# CoinControllerV1.net
KiCad netlist of a schematic drawn in EAGLE
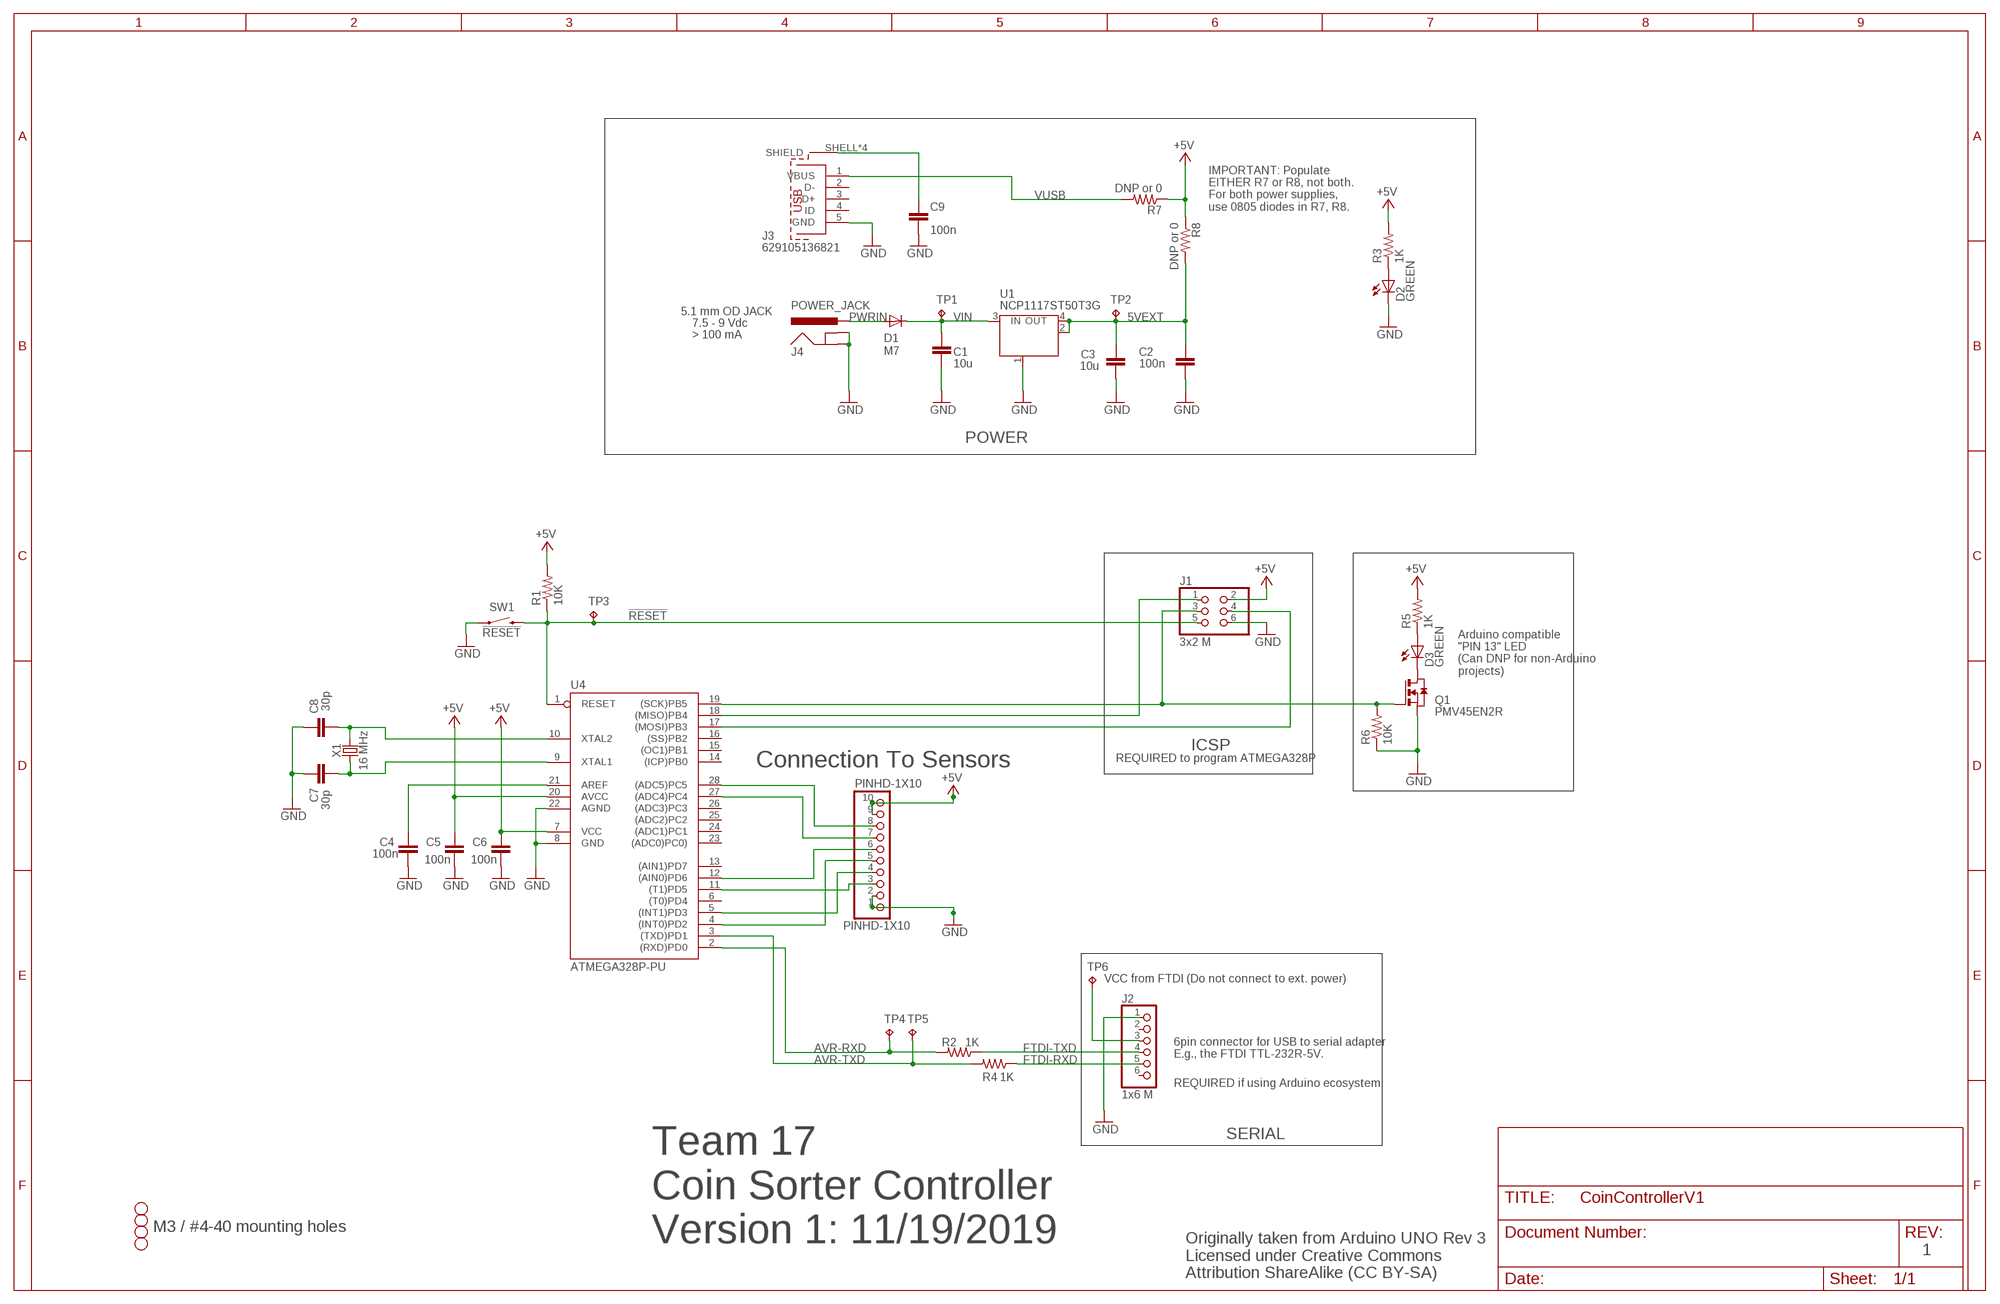
[diagram p0: schematic, sheet 1]

(export (version "E")
  (design (tool "Eeschema 10.0.6"))
  (components
    (comp (ref "C1")
      (value "10u")
      (footprint "eagle-import:C0805K")
      (fields (field (name "MFR") "Samsung") (field (name "MPN") "CL21A106KOQNNNG"))
      (libsource (lib "eagle-import") (part "C-EUC0805K"))
    )
    (comp (ref "C2")
      (value "100n")
      (footprint "eagle-import:C0805K")
      (fields (field (name "MFR") "Samsung") (field (name "MPN") "CL21B104KBCNNNC"))
      (libsource (lib "eagle-import") (part "C-EUC0805K"))
    )
    (comp (ref "C3")
      (value "10u")
      (footprint "eagle-import:C0805K")
      (fields (field (name "MFR") "Samsung") (field (name "MPN") "CL21A106KOQNNNG"))
      (libsource (lib "eagle-import") (part "C-EUC0805K"))
    )
    (comp (ref "C4")
      (value "100n")
      (footprint "eagle-import:C0805K")
      (fields (field (name "MFR") "Samsung") (field (name "MPN") "CL21B104KBCNNNC"))
      (libsource (lib "eagle-import") (part "C-EUC0805K"))
    )
    (comp (ref "C5")
      (value "100n")
      (footprint "eagle-import:C0805K")
      (fields (field (name "MFR") "Samsung") (field (name "MPN") "CL21B104KBCNNNC"))
      (libsource (lib "eagle-import") (part "C-EUC0805K"))
    )
    (comp (ref "C6")
      (value "100n")
      (footprint "eagle-import:C0805K")
      (fields (field (name "MFR") "Samsung") (field (name "MPN") "CL21B104KBCNNNC"))
      (libsource (lib "eagle-import") (part "C-EUC0805K"))
    )
    (comp (ref "C7")
      (value "30p")
      (footprint "eagle-import:C0805K")
      (fields (field (name "MFR") "Samsung") (field (name "MPN") "CL21C180JBANNNC"))
      (libsource (lib "eagle-import") (part "C-EUC0805K"))
    )
    (comp (ref "C8")
      (value "30p")
      (footprint "eagle-import:C0805K")
      (fields (field (name "MFR") "Samsung") (field (name "MPN") "CL21C300JBANNNC"))
      (libsource (lib "eagle-import") (part "C-EUC0805K"))
    )
    (comp (ref "C9")
      (value "100n")
      (footprint "eagle-import:C0805K")
      (fields (field (name "MFR") "Samsung") (field (name "MPN") "CL21B104KBCNNNC"))
      (libsource (lib "eagle-import") (part "C-EUC0805K"))
    )
    (comp (ref "D1")
      (value "M7")
      (footprint "eagle-import:SMB")
      (fields (field (name "MFR") "SMC Diode") (field (name "MPN") "10BQ030TR"))
      (libsource (lib "eagle-import") (part "DIODE-SMB"))
    )
    (comp (ref "D2")
      (value "GREEN")
      (footprint "eagle-import:CHIP-LED0805")
      (fields (field (name "MFR") "Würth Elektronik") (field (name "MPN") "150080GS75000"))
      (libsource (lib "eagle-import") (part "LEDCHIP-LED0805"))
    )
    (comp (ref "D3")
      (value "GREEN")
      (footprint "eagle-import:CHIP-LED0805")
      (fields (field (name "MFR") "Würth Elektronik") (field (name "MPN") "150080GS75000"))
      (libsource (lib "eagle-import") (part "LEDCHIP-LED0805"))
    )
    (comp (ref "H1")
      (value "STAND-OFF")
      (footprint "eagle-import:STAND-OFF")
      (libsource (lib "eagle-import") (part "STAND-OFF"))
    )
    (comp (ref "H2")
      (value "STAND-OFF")
      (footprint "eagle-import:STAND-OFF")
      (libsource (lib "eagle-import") (part "STAND-OFF"))
    )
    (comp (ref "H3")
      (value "STAND-OFF")
      (footprint "eagle-import:STAND-OFF")
      (libsource (lib "eagle-import") (part "STAND-OFF"))
    )
    (comp (ref "H4")
      (value "STAND-OFF")
      (footprint "eagle-import:STAND-OFF")
      (libsource (lib "eagle-import") (part "STAND-OFF"))
    )
    (comp (ref "J1")
      (value "3x2 M")
      (footprint "eagle-import:2X03")
      (fields (field (name "MFR") "Harwin") (field (name "MPN") "M20-9980345"))
      (libsource (lib "eagle-import") (part "PINHD-2X3"))
    )
    (comp (ref "J2")
      (value "1x6 M")
      (footprint "eagle-import:1X06")
      (fields (field (name "MFR") "Sullins") (field (name "MPN") "PRPC006SAAN-RC"))
      (libsource (lib "eagle-import") (part "PINHD-1X6"))
    )
    (comp (ref "J3")
      (value "629105136821")
      (footprint "eagle-import:629105136821")
      (fields (field (name "MFR") "Wurth"))
      (libsource (lib "eagle-import") (part "629105136821"))
    )
    (comp (ref "J4")
      (value "POWER_JACK")
      (footprint "eagle-import:POWER_JACK_PTH")
      (fields (field (name "MFR") "CUI") (field (name "MPN") "PJ-202A"))
      (libsource (lib "eagle-import") (part "POWER_JACK"))
    )
    (comp (ref "PINHD-1X10")
      (value "PINHD-1X10")
      (footprint "eagle-import:1X10-BIG")
      (libsource (lib "eagle-import") (part "PINHD-1X10"))
    )
    (comp (ref "Q1")
      (value "PMV45EN2R")
      (footprint "eagle-import:SOT-23")
      (fields (field (name "MFR") "Nexperia") (field (name "MPN") "PMV45EN2R"))
      (libsource (lib "eagle-import") (part "NMOSSOT23"))
    )
    (comp (ref "R1")
      (value "10K")
      (footprint "eagle-import:R0805")
      (fields (field (name "MFR") "Yageo") (field (name "MPN") "RC0805FR-0710KL"))
      (libsource (lib "eagle-import") (part "R-US_R0805"))
    )
    (comp (ref "R2")
      (value "1K")
      (footprint "eagle-import:R0805")
      (fields (field (name "MFR") "Yageo") (field (name "MPN") "RC0805FR-071KL"))
      (libsource (lib "eagle-import") (part "R-US_R0805"))
    )
    (comp (ref "R3")
      (value "1K")
      (footprint "eagle-import:R0805")
      (fields (field (name "MFR") "Yageo") (field (name "MPN") "RC0805FR-071KL"))
      (libsource (lib "eagle-import") (part "R-US_R0805"))
    )
    (comp (ref "R4")
      (value "1K")
      (footprint "eagle-import:R0805")
      (fields (field (name "MFR") "Yageo") (field (name "MPN") "RC0805FR-071KL"))
      (libsource (lib "eagle-import") (part "R-US_R0805"))
    )
    (comp (ref "R5")
      (value "1K")
      (footprint "eagle-import:R0805")
      (fields (field (name "MFR") "Yageo") (field (name "MPN") "RC0805FR-071KL"))
      (libsource (lib "eagle-import") (part "R-US_R0805"))
    )
    (comp (ref "R6")
      (value "10K")
      (footprint "eagle-import:R0805")
      (fields (field (name "MFR") "Yageo") (field (name "MPN") "RC0805FR-0710KL"))
      (libsource (lib "eagle-import") (part "R-US_R0805"))
    )
    (comp (ref "R7")
      (value "DNP or 0")
      (footprint "eagle-import:R0805")
      (fields (field (name "MFR") "Yageo") (field (name "MPN") "RC0805JR-070RL"))
      (libsource (lib "eagle-import") (part "R-US_R0805"))
    )
    (comp (ref "R8")
      (value "DNP or 0")
      (footprint "eagle-import:R0805")
      (fields (field (name "MFR") "Yageo") (field (name "MPN") "RC0805JR-070RL"))
      (libsource (lib "eagle-import") (part "R-US_R0805"))
    )
    (comp (ref "SW1")
      (value "!RESET")
      (footprint "eagle-import:TACTILE_SWITCH_SMD")
      (fields (field (name "MFR") "C&K") (field (name "MPN") "RS-187R05A2-DS MT RT"))
      (libsource (lib "eagle-import") (part "SWITCH-MOMENTARY-2SMD"))
    )
    (comp (ref "TP1")
      (value "TPPAD1-13")
      (footprint "eagle-import:P1-13")
      (libsource (lib "eagle-import") (part "TPPAD1-13"))
    )
    (comp (ref "TP2")
      (value "TPPAD1-13")
      (footprint "eagle-import:P1-13")
      (libsource (lib "eagle-import") (part "TPPAD1-13"))
    )
    (comp (ref "TP3")
      (value "TPPAD1-13")
      (footprint "eagle-import:P1-13")
      (libsource (lib "eagle-import") (part "TPPAD1-13"))
    )
    (comp (ref "TP4")
      (value "TPPAD1-13")
      (footprint "eagle-import:P1-13")
      (libsource (lib "eagle-import") (part "TPPAD1-13"))
    )
    (comp (ref "TP5")
      (value "TPPAD1-13")
      (footprint "eagle-import:P1-13")
      (libsource (lib "eagle-import") (part "TPPAD1-13"))
    )
    (comp (ref "TP6")
      (value "TPPAD1-13")
      (footprint "eagle-import:P1-13")
      (libsource (lib "eagle-import") (part "TPPAD1-13"))
    )
    (comp (ref "U1")
      (value "NCP1117ST50T3G")
      (footprint "eagle-import:SOT223")
      (fields (field (name "MFR") "ON Semiconductor"))
      (libsource (lib "eagle-import") (part "MC33269ST-3.3T3"))
    )
    (comp (ref "U4")
      (value "ATMEGA328P-PU")
      (footprint "eagle-import:DIL28-3")
      (fields (field (name "MFR") "Microchip"))
      (libsource (lib "eagle-import") (part "ATMEGA328P-PU"))
    )
    (comp (ref "X1")
      (value "16 MHz")
      (footprint "eagle-import:HC49UP")
      (fields (field (name "MFR") "ECS") (field (name "MPN") "ECS-160-18-5PX-TR"))
      (libsource (lib "eagle-import") (part "CRYSTALSMD-HC49UP"))
    )
  )
  (nets
    (net (code "1") (name "+5V") (class "Default")
      (node (ref "C5") (pin "2") (pinfunction "2_2") (pintype "passive"))
      (node (ref "C6") (pin "2") (pinfunction "2_2") (pintype "passive"))
      (node (ref "J1") (pin "2") (pinfunction "2_2") (pintype "passive"))
      (node (ref "PINHD-1X10") (pin "10") (pinfunction "10_10") (pintype "passive"))
      (node (ref "PINHD-1X10") (pin "9") (pinfunction "9_9") (pintype "passive"))
      (node (ref "R1") (pin "2") (pinfunction "2_2") (pintype "passive"))
      (node (ref "R3") (pin "2") (pinfunction "2_2") (pintype "passive"))
      (node (ref "R5") (pin "2") (pinfunction "2_2") (pintype "passive"))
      (node (ref "R7") (pin "1") (pinfunction "1_1") (pintype "passive"))
      (node (ref "R8") (pin "1") (pinfunction "1_1") (pintype "passive"))
      (node (ref "U4") (pin "20") (pinfunction "AVCC_20") (pintype "power_in"))
      (node (ref "U4") (pin "7") (pinfunction "VCC_7") (pintype "power_in"))
    )
    (net (code "2") (name "/5VEXT") (class "Default")
      (node (ref "C2") (pin "2") (pinfunction "2_2") (pintype "passive"))
      (node (ref "C3") (pin "1") (pinfunction "1_1") (pintype "passive"))
      (node (ref "R8") (pin "2") (pinfunction "2_2") (pintype "passive"))
      (node (ref "TP2") (pin "TP") (pinfunction "TP_TP") (pintype "input"))
      (node (ref "U1") (pin "2") (pinfunction "OUT_2") (pintype "passive"))
      (node (ref "U1") (pin "4") (pinfunction "OUT_4") (pintype "passive"))
    )
    (net (code "3") (name "/AVR-RXD") (class "Default")
      (node (ref "R2") (pin "2") (pinfunction "2_2") (pintype "passive"))
      (node (ref "TP4") (pin "TP") (pinfunction "TP_TP") (pintype "input"))
      (node (ref "U4") (pin "2") (pinfunction "(RXD)PD0_2") (pintype "bidirectional"))
    )
    (net (code "4") (name "/AVR-TXD") (class "Default")
      (node (ref "R4") (pin "2") (pinfunction "2_2") (pintype "passive"))
      (node (ref "TP5") (pin "TP") (pinfunction "TP_TP") (pintype "input"))
      (node (ref "U4") (pin "3") (pinfunction "(TXD)PD1_3") (pintype "bidirectional"))
    )
    (net (code "5") (name "/FTDI-RXD") (class "Default")
      (node (ref "J2") (pin "5") (pinfunction "5_5") (pintype "passive"))
      (node (ref "R4") (pin "1") (pinfunction "1_1") (pintype "passive"))
    )
    (net (code "6") (name "/FTDI-TXD") (class "Default")
      (node (ref "J2") (pin "4") (pinfunction "4_4") (pintype "passive"))
      (node (ref "R2") (pin "1") (pinfunction "1_1") (pintype "passive"))
    )
    (net (code "7") (name "/PWRIN") (class "Default")
      (node (ref "D1") (pin "A") (pinfunction "A_A") (pintype "passive"))
      (node (ref "J4") (pin "PWR") (pinfunction "PWR_PWR") (pintype "bidirectional"))
    )
    (net (code "8") (name "/VIN") (class "Default")
      (node (ref "C1") (pin "1") (pinfunction "1_1") (pintype "passive"))
      (node (ref "D1") (pin "C") (pinfunction "C_C") (pintype "passive"))
      (node (ref "TP1") (pin "TP") (pinfunction "TP_TP") (pintype "input"))
      (node (ref "U1") (pin "3") (pinfunction "IN_3") (pintype "input"))
    )
    (net (code "9") (name "/VUSB") (class "Default")
      (node (ref "J3") (pin "1") (pinfunction "VBUS_1") (pintype "passive"))
      (node (ref "R7") (pin "2") (pinfunction "2_2") (pintype "passive"))
    )
    (net (code "10") (name "/~{RESET}") (class "Default")
      (node (ref "J1") (pin "5") (pinfunction "5_5") (pintype "passive"))
      (node (ref "R1") (pin "1") (pinfunction "1_1") (pintype "passive"))
      (node (ref "SW1") (pin "3") (pinfunction "2_3") (pintype "passive"))
      (node (ref "TP3") (pin "TP") (pinfunction "TP_TP") (pintype "input"))
      (node (ref "U4") (pin "1") (pinfunction "RESET_1") (pintype "input"))
    )
    (net (code "11") (name "GND") (class "Default")
      (node (ref "C1") (pin "2") (pinfunction "2_2") (pintype "passive"))
      (node (ref "C2") (pin "1") (pinfunction "1_1") (pintype "passive"))
      (node (ref "C3") (pin "2") (pinfunction "2_2") (pintype "passive"))
      (node (ref "C4") (pin "1") (pinfunction "1_1") (pintype "passive"))
      (node (ref "C5") (pin "1") (pinfunction "1_1") (pintype "passive"))
      (node (ref "C6") (pin "1") (pinfunction "1_1") (pintype "passive"))
      (node (ref "C7") (pin "2") (pinfunction "2_2") (pintype "passive"))
      (node (ref "C8") (pin "2") (pinfunction "2_2") (pintype "passive"))
      (node (ref "C9") (pin "1") (pinfunction "1_1") (pintype "passive"))
      (node (ref "D2") (pin "C") (pinfunction "C_C") (pintype "passive"))
      (node (ref "J1") (pin "6") (pinfunction "6_6") (pintype "passive"))
      (node (ref "J2") (pin "1") (pinfunction "1_1") (pintype "passive"))
      (node (ref "J3") (pin "5") (pinfunction "GND_5") (pintype "passive"))
      (node (ref "J4") (pin "GND") (pinfunction "GND_GND") (pintype "bidirectional"))
      (node (ref "J4") (pin "GNDBREAK") (pinfunction "GNDBREAK_GNDBREAK") (pintype "bidirectional"))
      (node (ref "PINHD-1X10") (pin "1") (pinfunction "1_1") (pintype "passive"))
      (node (ref "PINHD-1X10") (pin "2") (pinfunction "2_2") (pintype "passive"))
      (node (ref "Q1") (pin "2") (pinfunction "S_2") (pintype "passive"))
      (node (ref "R6") (pin "1") (pinfunction "1_1") (pintype "passive"))
      (node (ref "SW1") (pin "1") (pinfunction "1_1") (pintype "passive"))
      (node (ref "U1") (pin "1") (pinfunction "GND/ADJ_1") (pintype "input"))
      (node (ref "U4") (pin "22") (pinfunction "AGND_22") (pintype "power_in"))
      (node (ref "U4") (pin "8") (pinfunction "GND_8") (pintype "power_in"))
    )
    (net (code "12") (name "Net-(C9-Pad2)") (class "Default")
      (node (ref "C9") (pin "2") (pinfunction "2_2") (pintype "passive"))
      (node (ref "J3") (pin "SHELL") (pinfunction "SHIELD_SHELL") (pintype "passive"))
      (node (ref "J3") (pin "SHELL1") (pinfunction "SHIELD_SHELL1") (pintype "passive"))
      (node (ref "J3") (pin "SHELL2") (pinfunction "SHIELD_SHELL2") (pintype "passive"))
      (node (ref "J3") (pin "SHELL3") (pinfunction "SHIELD_SHELL3") (pintype "passive"))
    )
    (net (code "13") (name "Net-(D2-PadA)") (class "Default")
      (node (ref "D2") (pin "A") (pinfunction "A_A") (pintype "passive"))
      (node (ref "R3") (pin "1") (pinfunction "1_1") (pintype "passive"))
    )
    (net (code "14") (name "Net-(D3-PadA)") (class "Default")
      (node (ref "D3") (pin "A") (pinfunction "A_A") (pintype "passive"))
      (node (ref "R5") (pin "1") (pinfunction "1_1") (pintype "passive"))
    )
    (net (code "15") (name "Net-(J2-Pad3)") (class "Default")
      (node (ref "J2") (pin "3") (pinfunction "3_3") (pintype "passive"))
      (node (ref "TP6") (pin "TP") (pinfunction "TP_TP") (pintype "input"))
    )
    (net (code "16") (name "Net-(Q1-D)") (class "Default")
      (node (ref "D3") (pin "C") (pinfunction "C_C") (pintype "passive"))
      (node (ref "Q1") (pin "1") (pinfunction "D_1") (pintype "passive"))
    )
    (net (code "17") (name "Net-(Q1-G)") (class "Default")
      (node (ref "J1") (pin "3") (pinfunction "3_3") (pintype "passive"))
      (node (ref "Q1") (pin "3") (pinfunction "G_3") (pintype "passive"))
      (node (ref "R6") (pin "2") (pinfunction "2_2") (pintype "passive"))
      (node (ref "U4") (pin "19") (pinfunction "(SCK)PB5_19") (pintype "bidirectional"))
    )
    (net (code "18") (name "Net-(U4-(ADC4)PC4)") (class "Default")
      (node (ref "PINHD-1X10") (pin "7") (pinfunction "7_7") (pintype "passive"))
      (node (ref "U4") (pin "27") (pinfunction "(ADC4)PC4_27") (pintype "bidirectional"))
    )
    (net (code "19") (name "Net-(U4-(ADC5)PC5)") (class "Default")
      (node (ref "PINHD-1X10") (pin "8") (pinfunction "8_8") (pintype "passive"))
      (node (ref "U4") (pin "28") (pinfunction "(ADC5)PC5_28") (pintype "bidirectional"))
    )
    (net (code "20") (name "Net-(U4-(AIN0)PD6)") (class "Default")
      (node (ref "PINHD-1X10") (pin "6") (pinfunction "6_6") (pintype "passive"))
      (node (ref "U4") (pin "12") (pinfunction "(AIN0)PD6_12") (pintype "bidirectional"))
    )
    (net (code "21") (name "Net-(U4-(INT0)PD2)") (class "Default")
      (node (ref "PINHD-1X10") (pin "5") (pinfunction "5_5") (pintype "passive"))
      (node (ref "U4") (pin "4") (pinfunction "(INT0)PD2_4") (pintype "bidirectional"))
    )
    (net (code "22") (name "Net-(U4-(INT1)PD3)") (class "Default")
      (node (ref "PINHD-1X10") (pin "4") (pinfunction "4_4") (pintype "passive"))
      (node (ref "U4") (pin "5") (pinfunction "(INT1)PD3_5") (pintype "bidirectional"))
    )
    (net (code "23") (name "Net-(U4-(MISO)PB4)") (class "Default")
      (node (ref "J1") (pin "1") (pinfunction "1_1") (pintype "passive"))
      (node (ref "U4") (pin "18") (pinfunction "(MISO)PB4_18") (pintype "bidirectional"))
    )
    (net (code "24") (name "Net-(U4-(MOSI)PB3)") (class "Default")
      (node (ref "J1") (pin "4") (pinfunction "4_4") (pintype "passive"))
      (node (ref "U4") (pin "17") (pinfunction "(MOSI)PB3_17") (pintype "bidirectional"))
    )
    (net (code "25") (name "Net-(U4-(T1)PD5)") (class "Default")
      (node (ref "PINHD-1X10") (pin "3") (pinfunction "3_3") (pintype "passive"))
      (node (ref "U4") (pin "11") (pinfunction "(T1)PD5_11") (pintype "bidirectional"))
    )
    (net (code "26") (name "Net-(U4-AREF)") (class "Default")
      (node (ref "C4") (pin "2") (pinfunction "2_2") (pintype "passive"))
      (node (ref "U4") (pin "21") (pinfunction "AREF_21") (pintype "passive"))
    )
    (net (code "27") (name "Net-(U4-XTAL1)") (class "Default")
      (node (ref "C7") (pin "1") (pinfunction "1_1") (pintype "passive"))
      (node (ref "U4") (pin "9") (pinfunction "XTAL1_9") (pintype "bidirectional"))
      (node (ref "X1") (pin "1") (pinfunction "1_1") (pintype "passive"))
    )
    (net (code "28") (name "Net-(U4-XTAL2)") (class "Default")
      (node (ref "C8") (pin "1") (pinfunction "1_1") (pintype "passive"))
      (node (ref "U4") (pin "10") (pinfunction "XTAL2_10") (pintype "bidirectional"))
      (node (ref "X1") (pin "2") (pinfunction "2_2") (pintype "passive"))
    )
    (net (code "29") (name "unconnected-(J2-Pad2)") (class "Default")
      (node (ref "J2") (pin "2") (pinfunction "2_2") (pintype "passive"))
    )
    (net (code "30") (name "unconnected-(J2-Pad6)") (class "Default")
      (node (ref "J2") (pin "6") (pinfunction "6_6") (pintype "passive"))
    )
    (net (code "31") (name "unconnected-(J3-D+-Pad3)") (class "Default")
      (node (ref "J3") (pin "3") (pinfunction "D+_3") (pintype "passive"))
    )
    (net (code "32") (name "unconnected-(J3-D--Pad2)") (class "Default")
      (node (ref "J3") (pin "2") (pinfunction "D-_2") (pintype "passive"))
    )
    (net (code "33") (name "unconnected-(J3-ID-Pad4)") (class "Default")
      (node (ref "J3") (pin "4") (pinfunction "ID_4") (pintype "passive"))
    )
    (net (code "34") (name "unconnected-(U4-(ADC0)PC0)-Pad23)") (class "Default")
      (node (ref "U4") (pin "23") (pinfunction "(ADC0)PC0)_23") (pintype "bidirectional"))
    )
    (net (code "35") (name "unconnected-(U4-(ADC1)PC1-Pad24)") (class "Default")
      (node (ref "U4") (pin "24") (pinfunction "(ADC1)PC1_24") (pintype "bidirectional"))
    )
    (net (code "36") (name "unconnected-(U4-(ADC2)PC2-Pad25)") (class "Default")
      (node (ref "U4") (pin "25") (pinfunction "(ADC2)PC2_25") (pintype "bidirectional"))
    )
    (net (code "37") (name "unconnected-(U4-(ADC3)PC3-Pad26)") (class "Default")
      (node (ref "U4") (pin "26") (pinfunction "(ADC3)PC3_26") (pintype "bidirectional"))
    )
    (net (code "38") (name "unconnected-(U4-(AIN1)PD7-Pad13)") (class "Default")
      (node (ref "U4") (pin "13") (pinfunction "(AIN1)PD7_13") (pintype "bidirectional"))
    )
    (net (code "39") (name "unconnected-(U4-(ICP)PB0-Pad14)") (class "Default")
      (node (ref "U4") (pin "14") (pinfunction "(ICP)PB0_14") (pintype "bidirectional"))
    )
    (net (code "40") (name "unconnected-(U4-(OC1)PB1-Pad15)") (class "Default")
      (node (ref "U4") (pin "15") (pinfunction "(OC1)PB1_15") (pintype "bidirectional"))
    )
    (net (code "41") (name "unconnected-(U4-(SS)PB2-Pad16)") (class "Default")
      (node (ref "U4") (pin "16") (pinfunction "(SS)PB2_16") (pintype "bidirectional"))
    )
    (net (code "42") (name "unconnected-(U4-(T0)PD4-Pad6)") (class "Default")
      (node (ref "U4") (pin "6") (pinfunction "(T0)PD4_6") (pintype "bidirectional"))
    )
  )
)
